# microzed_sd_v0_4.net
KiCad netlist of a schematic drawn in EAGLE
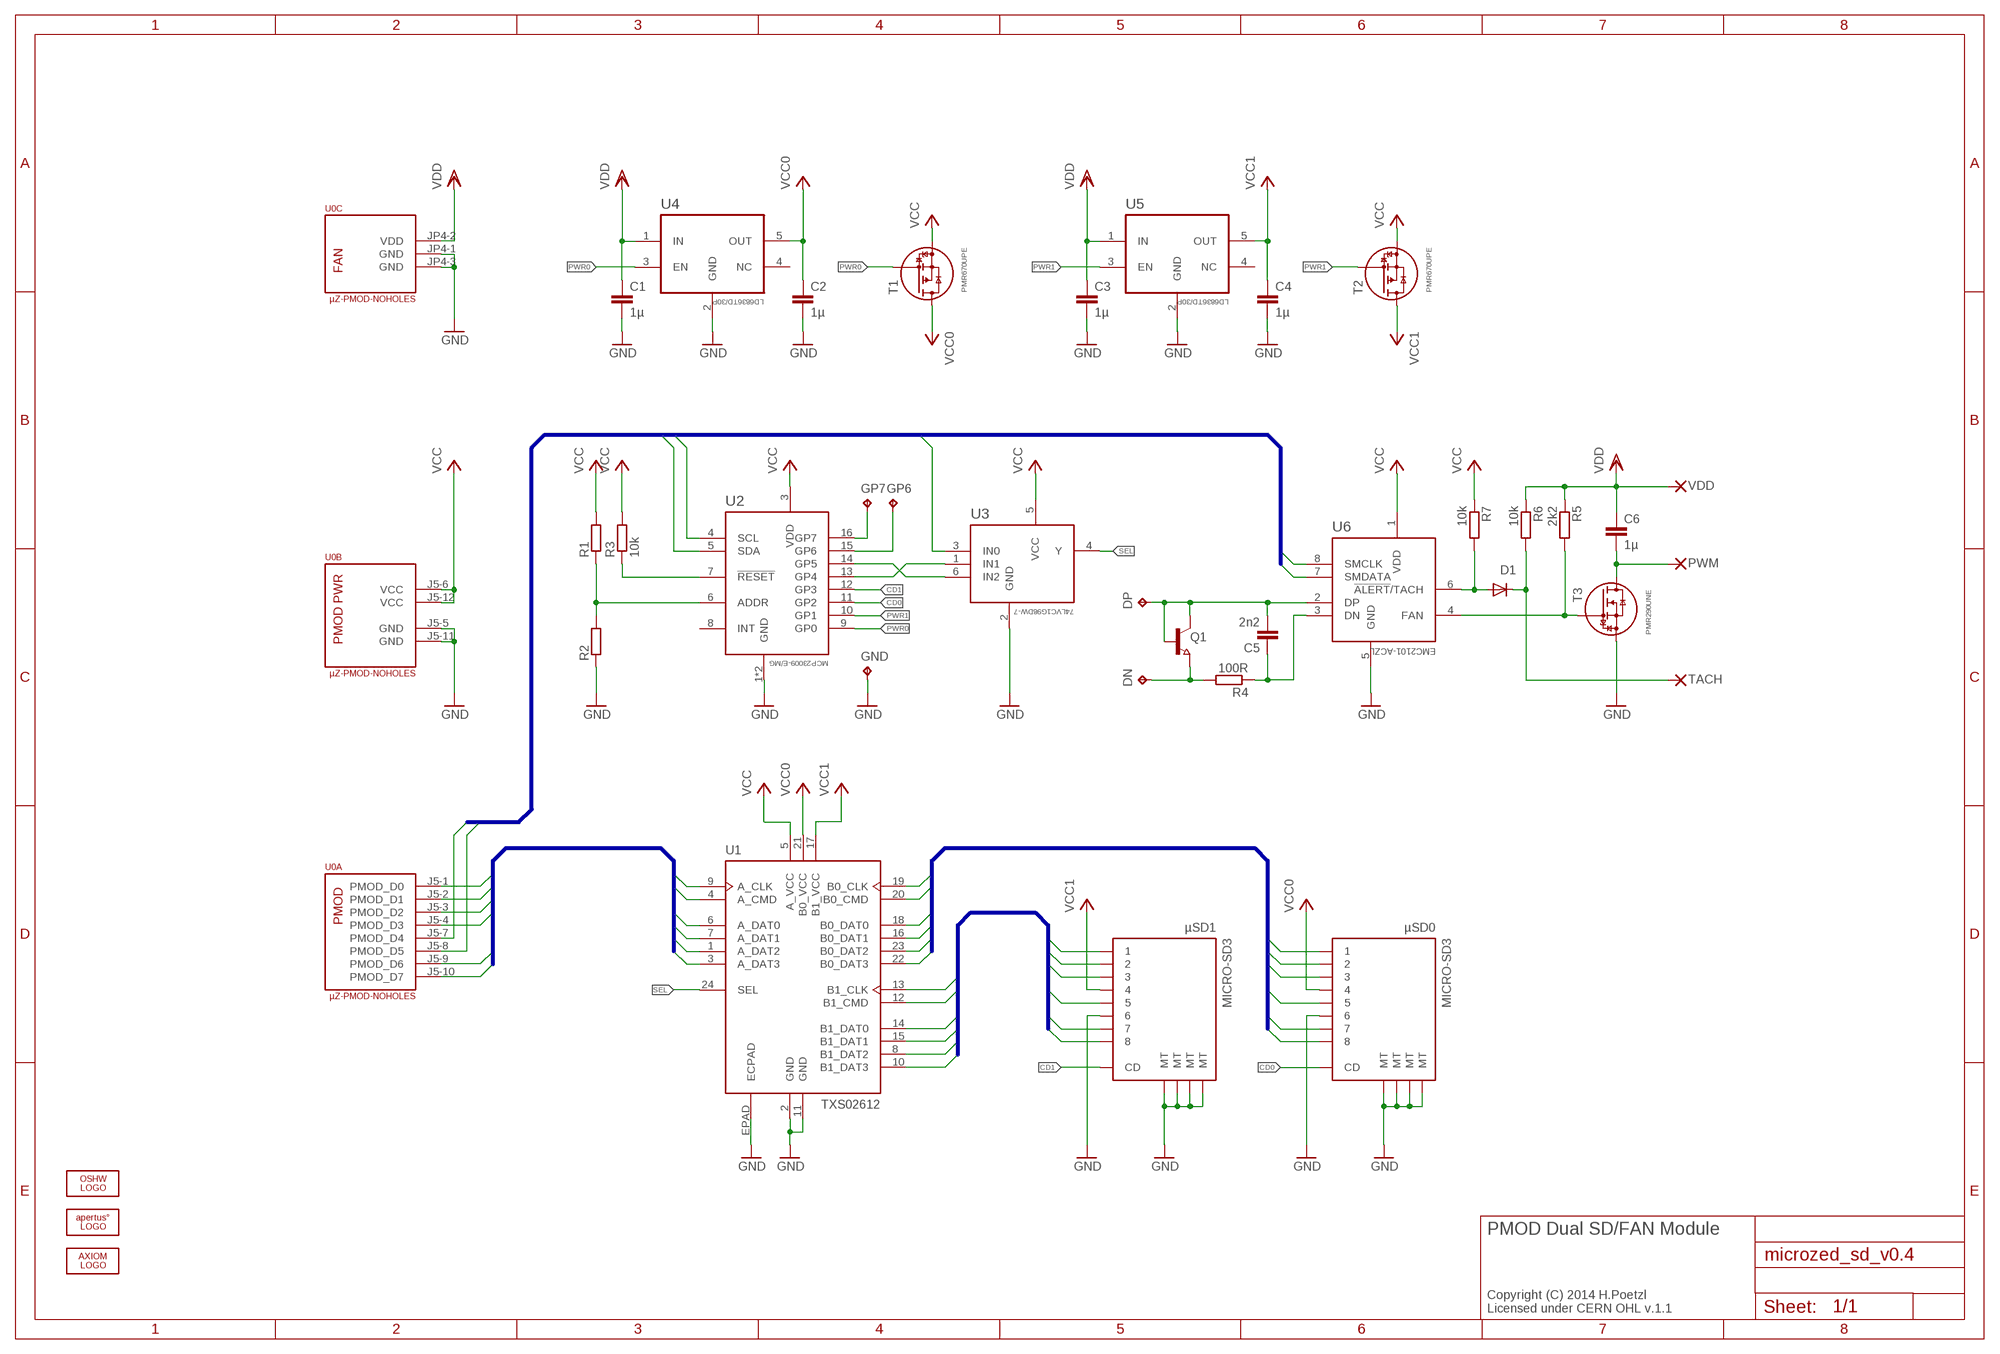
[diagram p0: schematic, sheet 1]

(export (version "E")
  (design (tool "Eeschema 10.0.6"))
  (components
    (comp (ref "C1")
      (value "1µ")
      (footprint "eagle-import:C0402K")
      (libsource (lib "eagle-import") (part "C-EUC0402K"))
    )
    (comp (ref "C2")
      (value "1µ")
      (footprint "eagle-import:C0402K")
      (libsource (lib "eagle-import") (part "C-EUC0402K"))
    )
    (comp (ref "C3")
      (value "1µ")
      (footprint "eagle-import:C0402K")
      (libsource (lib "eagle-import") (part "C-EUC0402K"))
    )
    (comp (ref "C4")
      (value "1µ")
      (footprint "eagle-import:C0402K")
      (libsource (lib "eagle-import") (part "C-EUC0402K"))
    )
    (comp (ref "C5")
      (value "2n2")
      (footprint "eagle-import:C0402K")
      (libsource (lib "eagle-import") (part "C-EUC0402K"))
    )
    (comp (ref "C6")
      (value "1µ")
      (footprint "eagle-import:C0402K")
      (libsource (lib "eagle-import") (part "C-EUC0402K"))
    )
    (comp (ref "D1")
      (value "DIODE-MICROMELF-W")
      (footprint "eagle-import:MICROMELF-W")
      (libsource (lib "eagle-import") (part "DIODE-MICROMELF-W"))
    )
    (comp (ref "DN")
      (value "TPTP20R")
      (footprint "eagle-import:TP20R")
      (libsource (lib "eagle-import") (part "TPTP20R"))
    )
    (comp (ref "DP")
      (value "TPTP20R")
      (footprint "eagle-import:TP20R")
      (libsource (lib "eagle-import") (part "TPTP20R"))
    )
    (comp (ref "GND")
      (value "TPTP20R")
      (footprint "eagle-import:TP20R")
      (libsource (lib "eagle-import") (part "TPTP20R"))
    )
    (comp (ref "GP6")
      (value "TPTP20R")
      (footprint "eagle-import:TP20R")
      (libsource (lib "eagle-import") (part "TPTP20R"))
    )
    (comp (ref "GP7")
      (value "TPTP20R")
      (footprint "eagle-import:TP20R")
      (libsource (lib "eagle-import") (part "TPTP20R"))
    )
    (comp (ref "LOGO1")
      (value "OSHW_LOGO_FILLX0100-NT")
      (footprint "eagle-import:OSHW_FILLX100_NOTEXT")
      (libsource (lib "eagle-import") (part "OSHW_LOGO_FILLX0100-NT"))
    )
    (comp (ref "PWM")
      (value "WIREPAD2,15/1,0")
      (footprint "eagle-import:2,15_1,0")
      (libsource (lib "eagle-import") (part "WIREPAD2,15/1,0"))
    )
    (comp (ref "Q1")
      (value "NPN-TRANSISTOR_SOT23")
      (footprint "eagle-import:SOT23")
      (libsource (lib "eagle-import") (part "NPN-TRANSISTOR_SOT23"))
    )
    (comp (ref "R1")
      (value "R-EU_R0603")
      (footprint "eagle-import:R0603")
      (libsource (lib "eagle-import") (part "R-EU_R0603"))
    )
    (comp (ref "R2")
      (value "R-EU_R0603")
      (footprint "eagle-import:R0603")
      (libsource (lib "eagle-import") (part "R-EU_R0603"))
    )
    (comp (ref "R3")
      (value "10k")
      (footprint "eagle-import:R0603")
      (libsource (lib "eagle-import") (part "R-EU_R0603"))
    )
    (comp (ref "R4")
      (value "100R")
      (footprint "eagle-import:R0402")
      (libsource (lib "eagle-import") (part "R-EU_R0402"))
    )
    (comp (ref "R5")
      (value "2k2")
      (footprint "eagle-import:R0402")
      (libsource (lib "eagle-import") (part "R-EU_R0402"))
    )
    (comp (ref "R6")
      (value "10k")
      (footprint "eagle-import:R0402")
      (libsource (lib "eagle-import") (part "R-EU_R0402"))
    )
    (comp (ref "R7")
      (value "10k")
      (footprint "eagle-import:R0402")
      (libsource (lib "eagle-import") (part "R-EU_R0402"))
    )
    (comp (ref "T1")
      (value "PMR670UPE")
      (footprint "eagle-import:SOT416")
      (libsource (lib "eagle-import") (part "PMR670UPE"))
    )
    (comp (ref "T2")
      (value "PMR670UPE")
      (footprint "eagle-import:SOT416")
      (libsource (lib "eagle-import") (part "PMR670UPE"))
    )
    (comp (ref "T3")
      (value "PMR290UNE")
      (footprint "eagle-import:SOT416")
      (libsource (lib "eagle-import") (part "PMR290UNE"))
    )
    (comp (ref "TACH")
      (value "WIREPAD2,15/1,0")
      (footprint "eagle-import:2,15_1,0")
      (libsource (lib "eagle-import") (part "WIREPAD2,15/1,0"))
    )
    (comp (ref "U$1")
      (value "APERTUS_LOGO334X100")
      (footprint "eagle-import:APERTUS_LOGO_334X100")
      (libsource (lib "eagle-import") (part "APERTUS_LOGO334X100"))
    )
    (comp (ref "U$13")
      (value "AXIOM_LOGO525X80")
      (footprint "eagle-import:AXIOM_LOGO_525X80")
      (libsource (lib "eagle-import") (part "AXIOM_LOGO525X80"))
    )
    (comp (ref "U0")
      (value "µZ-PMOD-NOHOLES")
      (footprint "eagle-import:µZ-TOP-NOHOLES")
      (libsource (lib "eagle-import") (part "µZ-PMOD-NOHOLES"))
    )
    (comp (ref "U1")
      (value "TXS02612")
      (footprint "eagle-import:S-PWQFN-N24")
      (libsource (lib "eagle-import") (part "TXS02612"))
    )
    (comp (ref "U2")
      (value "MCP23009-E/MG")
      (footprint "eagle-import:QFN50P300X300X80-17N")
      (libsource (lib "eagle-import") (part "MCP23009-E/MG"))
    )
    (comp (ref "U3")
      (value "74LVC1G98DW-7")
      (footprint "eagle-import:SOT65P210X110-6N")
      (libsource (lib "eagle-import") (part "74LVC1G98DW-7"))
    )
    (comp (ref "U4")
      (value "LD6836TD/30P")
      (footprint "eagle-import:SOT95P275X110-5N")
      (libsource (lib "eagle-import") (part "LD6836TD/30P"))
    )
    (comp (ref "U5")
      (value "LD6836TD/30P")
      (footprint "eagle-import:SOT95P275X110-5N")
      (libsource (lib "eagle-import") (part "LD6836TD/30P"))
    )
    (comp (ref "U6")
      (value "EMC2101-ACZL")
      (footprint "eagle-import:SOP65P490X110-8N")
      (fields (field (name "MPN") "EMC2101-ACZL-TR "))
      (libsource (lib "eagle-import") (part "EMC2101-ACZL"))
    )
    (comp (ref "VDD")
      (value "WIREPAD2,15/1,0")
      (footprint "eagle-import:2,15_1,0")
      (libsource (lib "eagle-import") (part "WIREPAD2,15/1,0"))
    )
    (comp (ref "µSD0")
      (value "MICRO-SD3")
      (footprint "eagle-import:TF-MICRO-SD_PP3")
      (libsource (lib "eagle-import") (part "MICRO-SD3"))
    )
    (comp (ref "µSD1")
      (value "MICRO-SD3")
      (footprint "eagle-import:TF-MICRO-SD_PP3")
      (libsource (lib "eagle-import") (part "MICRO-SD3"))
    )
  )
  (nets
    (net (code "1") (name "/A_CLK") (class "Default")
      (node (ref "U0") (pin "J5-4") (pinfunction "PMOD_D3_J5-4") (pintype "bidirectional"))
      (node (ref "U1") (pin "9") (pinfunction "A_CLK_9") (pintype "input"))
    )
    (net (code "2") (name "/A_CMD") (class "Default")
      (node (ref "U0") (pin "J5-3") (pinfunction "PMOD_D2_J5-3") (pintype "bidirectional"))
      (node (ref "U1") (pin "4") (pinfunction "A_CMD_4") (pintype "bidirectional"))
    )
    (net (code "3") (name "/A_DAT0") (class "Default")
      (node (ref "U0") (pin "J5-2") (pinfunction "PMOD_D1_J5-2") (pintype "bidirectional"))
      (node (ref "U1") (pin "6") (pinfunction "A_DAT0_6") (pintype "bidirectional"))
    )
    (net (code "4") (name "/A_DAT1") (class "Default")
      (node (ref "U0") (pin "J5-1") (pinfunction "PMOD_D0_J5-1") (pintype "bidirectional"))
      (node (ref "U1") (pin "7") (pinfunction "A_DAT1_7") (pintype "bidirectional"))
    )
    (net (code "5") (name "/A_DAT2") (class "Default")
      (node (ref "U0") (pin "J5-9") (pinfunction "PMOD_D6_J5-9") (pintype "bidirectional"))
      (node (ref "U1") (pin "1") (pinfunction "A_DAT2_1") (pintype "bidirectional"))
    )
    (net (code "6") (name "/A_DAT3") (class "Default")
      (node (ref "U0") (pin "J5-10") (pinfunction "PMOD_D7_J5-10") (pintype "bidirectional"))
      (node (ref "U1") (pin "3") (pinfunction "A_DAT3_3") (pintype "bidirectional"))
    )
    (net (code "7") (name "/B0_CLK") (class "Default")
      (node (ref "U1") (pin "19") (pinfunction "B0_CLK_19") (pintype "output"))
      (node (ref "µSD0") (pin "5") (pinfunction "5_5") (pintype "bidirectional"))
    )
    (net (code "8") (name "/B0_CMD") (class "Default")
      (node (ref "U1") (pin "20") (pinfunction "B0_CMD_20") (pintype "bidirectional"))
      (node (ref "µSD0") (pin "3") (pinfunction "3_3") (pintype "bidirectional"))
    )
    (net (code "9") (name "/B0_DAT0") (class "Default")
      (node (ref "U1") (pin "18") (pinfunction "B0_DAT0_18") (pintype "bidirectional"))
      (node (ref "µSD0") (pin "7") (pinfunction "7_7") (pintype "bidirectional"))
    )
    (net (code "10") (name "/B0_DAT1") (class "Default")
      (node (ref "U1") (pin "16") (pinfunction "B0_DAT1_16") (pintype "bidirectional"))
      (node (ref "µSD0") (pin "8") (pinfunction "8_8") (pintype "bidirectional"))
    )
    (net (code "11") (name "/B0_DAT2") (class "Default")
      (node (ref "U1") (pin "23") (pinfunction "B0_DAT2_23") (pintype "bidirectional"))
      (node (ref "µSD0") (pin "1") (pinfunction "1_1") (pintype "bidirectional"))
    )
    (net (code "12") (name "/B0_DAT3") (class "Default")
      (node (ref "U1") (pin "22") (pinfunction "B0_DAT3_22") (pintype "bidirectional"))
      (node (ref "µSD0") (pin "2") (pinfunction "2_2") (pintype "bidirectional"))
    )
    (net (code "13") (name "/B1_CLK") (class "Default")
      (node (ref "U1") (pin "13") (pinfunction "B1_CLK_13") (pintype "output"))
      (node (ref "µSD1") (pin "5") (pinfunction "5_5") (pintype "bidirectional"))
    )
    (net (code "14") (name "/B1_CMD") (class "Default")
      (node (ref "U1") (pin "12") (pinfunction "B1_CMD_12") (pintype "bidirectional"))
      (node (ref "µSD1") (pin "3") (pinfunction "3_3") (pintype "bidirectional"))
    )
    (net (code "15") (name "/B1_DAT0") (class "Default")
      (node (ref "U1") (pin "14") (pinfunction "B1_DAT0_14") (pintype "bidirectional"))
      (node (ref "µSD1") (pin "7") (pinfunction "7_7") (pintype "bidirectional"))
    )
    (net (code "16") (name "/B1_DAT1") (class "Default")
      (node (ref "U1") (pin "15") (pinfunction "B1_DAT1_15") (pintype "bidirectional"))
      (node (ref "µSD1") (pin "8") (pinfunction "8_8") (pintype "bidirectional"))
    )
    (net (code "17") (name "/B1_DAT2") (class "Default")
      (node (ref "U1") (pin "8") (pinfunction "B1_DAT2_8") (pintype "bidirectional"))
      (node (ref "µSD1") (pin "1") (pinfunction "1_1") (pintype "bidirectional"))
    )
    (net (code "18") (name "/B1_DAT3") (class "Default")
      (node (ref "U1") (pin "10") (pinfunction "B1_DAT3_10") (pintype "bidirectional"))
      (node (ref "µSD1") (pin "2") (pinfunction "2_2") (pintype "bidirectional"))
    )
    (net (code "19") (name "/SCL") (class "Default")
      (node (ref "U0") (pin "J5-7") (pinfunction "PMOD_D4_J5-7") (pintype "bidirectional"))
      (node (ref "U2") (pin "4") (pinfunction "SCL_4") (pintype "input"))
      (node (ref "U6") (pin "8") (pinfunction "SMCLK_8") (pintype "input"))
    )
    (net (code "20") (name "/SDA") (class "Default")
      (node (ref "U0") (pin "J5-8") (pinfunction "PMOD_D5_J5-8") (pintype "bidirectional"))
      (node (ref "U2") (pin "5") (pinfunction "SDA_5") (pintype "bidirectional"))
      (node (ref "U3") (pin "3") (pinfunction "IN0_3") (pintype "input"))
      (node (ref "U6") (pin "7") (pinfunction "SMDATA_7") (pintype "bidirectional"))
    )
    (net (code "21") (name "CD0") (class "Default")
      (node (ref "U2") (pin "11") (pinfunction "GP2_11") (pintype "bidirectional"))
      (node (ref "µSD0") (pin "CD") (pinfunction "CD_CD") (pintype "bidirectional"))
    )
    (net (code "22") (name "CD1") (class "Default")
      (node (ref "U2") (pin "12") (pinfunction "GP3_12") (pintype "bidirectional"))
      (node (ref "µSD1") (pin "CD") (pinfunction "CD_CD") (pintype "bidirectional"))
    )
    (net (code "23") (name "GND") (class "Default")
      (node (ref "C1") (pin "2") (pinfunction "2_2") (pintype "passive"))
      (node (ref "C2") (pin "2") (pinfunction "2_2") (pintype "passive"))
      (node (ref "C3") (pin "2") (pinfunction "2_2") (pintype "passive"))
      (node (ref "C4") (pin "2") (pinfunction "2_2") (pintype "passive"))
      (node (ref "GND") (pin "TP") (pinfunction "TP_TP") (pintype "input"))
      (node (ref "R2") (pin "1") (pinfunction "1_1") (pintype "passive"))
      (node (ref "T3") (pin "2") (pinfunction "S_2") (pintype "passive"))
      (node (ref "U0") (pin "J5-11") (pinfunction "GND_J5-11") (pintype "power_in"))
      (node (ref "U0") (pin "J5-5") (pinfunction "GND_J5-5") (pintype "power_in"))
      (node (ref "U0") (pin "JP4-1") (pinfunction "GND_JP4-1") (pintype "power_in"))
      (node (ref "U0") (pin "JP4-3") (pinfunction "GND_JP4-3") (pintype "power_in"))
      (node (ref "U1") (pin "11") (pinfunction "GND_11") (pintype "power_in"))
      (node (ref "U1") (pin "2") (pinfunction "GND_2") (pintype "power_in"))
      (node (ref "U1") (pin "EPAD") (pinfunction "ECPAD_EPAD") (pintype "power_in"))
      (node (ref "U2") (pin "1") (pinfunction "GND_1") (pintype "power_in"))
      (node (ref "U2") (pin "17") (pinfunction "GND_17") (pintype "power_in"))
      (node (ref "U3") (pin "2") (pinfunction "GND_2") (pintype "passive"))
      (node (ref "U4") (pin "2") (pinfunction "GND_2") (pintype "passive"))
      (node (ref "U5") (pin "2") (pinfunction "GND_2") (pintype "passive"))
      (node (ref "U6") (pin "5") (pinfunction "GND_5") (pintype "power_in"))
      (node (ref "µSD0") (pin "6") (pinfunction "6_6") (pintype "bidirectional"))
      (node (ref "µSD0") (pin "MT1") (pinfunction "MT_MT1") (pintype "power_in"))
      (node (ref "µSD0") (pin "MT2") (pinfunction "MT_MT2") (pintype "power_in"))
      (node (ref "µSD0") (pin "MT3") (pinfunction "MT_MT3") (pintype "power_in"))
      (node (ref "µSD0") (pin "MT4") (pinfunction "MT_MT4") (pintype "power_in"))
      (node (ref "µSD1") (pin "6") (pinfunction "6_6") (pintype "bidirectional"))
      (node (ref "µSD1") (pin "MT1") (pinfunction "MT_MT1") (pintype "power_in"))
      (node (ref "µSD1") (pin "MT2") (pinfunction "MT_MT2") (pintype "power_in"))
      (node (ref "µSD1") (pin "MT3") (pinfunction "MT_MT3") (pintype "power_in"))
      (node (ref "µSD1") (pin "MT4") (pinfunction "MT_MT4") (pintype "power_in"))
    )
    (net (code "24") (name "Net-(PWM-P)") (class "Default")
      (node (ref "C6") (pin "2") (pinfunction "2_2") (pintype "passive"))
      (node (ref "PWM") (pin "1") (pinfunction "P_1") (pintype "passive"))
      (node (ref "T3") (pin "3") (pinfunction "D_3") (pintype "passive"))
    )
    (net (code "25") (name "Net-(Q1-B)") (class "Default")
      (node (ref "C5") (pin "2") (pinfunction "2_2") (pintype "passive"))
      (node (ref "DP") (pin "TP") (pinfunction "TP_TP") (pintype "input"))
      (node (ref "Q1") (pin "1") (pinfunction "B_1") (pintype "passive"))
      (node (ref "Q1") (pin "3") (pinfunction "C_3") (pintype "passive"))
      (node (ref "U6") (pin "2") (pinfunction "DP_2") (pintype "passive"))
    )
    (net (code "26") (name "Net-(Q1-E)") (class "Default")
      (node (ref "DN") (pin "TP") (pinfunction "TP_TP") (pintype "input"))
      (node (ref "Q1") (pin "2") (pinfunction "E_2") (pintype "passive"))
      (node (ref "R4") (pin "2") (pinfunction "2_2") (pintype "passive"))
    )
    (net (code "27") (name "Net-(T3-G)") (class "Default")
      (node (ref "R5") (pin "2") (pinfunction "2_2") (pintype "passive"))
      (node (ref "T3") (pin "1") (pinfunction "G_1") (pintype "passive"))
      (node (ref "U6") (pin "4") (pinfunction "FAN_4") (pintype "output"))
    )
    (net (code "28") (name "Net-(TACH-P)") (class "Default")
      (node (ref "D1") (pin "C") (pinfunction "C_C") (pintype "passive"))
      (node (ref "R6") (pin "2") (pinfunction "2_2") (pintype "passive"))
      (node (ref "TACH") (pin "1") (pinfunction "P_1") (pintype "passive"))
    )
    (net (code "29") (name "Net-(U2-ADDR)") (class "Default")
      (node (ref "R1") (pin "1") (pinfunction "1_1") (pintype "passive"))
      (node (ref "R2") (pin "2") (pinfunction "2_2") (pintype "passive"))
      (node (ref "U2") (pin "6") (pinfunction "ADDR_6") (pintype "input"))
    )
    (net (code "30") (name "Net-(U2-GP4)") (class "Default")
      (node (ref "U2") (pin "13") (pinfunction "GP4_13") (pintype "bidirectional"))
      (node (ref "U3") (pin "1") (pinfunction "IN1_1") (pintype "input"))
    )
    (net (code "31") (name "Net-(U2-GP5)") (class "Default")
      (node (ref "U2") (pin "14") (pinfunction "GP5_14") (pintype "bidirectional"))
      (node (ref "U3") (pin "6") (pinfunction "IN2_6") (pintype "input"))
    )
    (net (code "32") (name "Net-(U2-GP6)") (class "Default")
      (node (ref "GP6") (pin "TP") (pinfunction "TP_TP") (pintype "input"))
      (node (ref "U2") (pin "15") (pinfunction "GP6_15") (pintype "bidirectional"))
    )
    (net (code "33") (name "Net-(U2-GP7)") (class "Default")
      (node (ref "GP7") (pin "TP") (pinfunction "TP_TP") (pintype "input"))
      (node (ref "U2") (pin "16") (pinfunction "GP7_16") (pintype "bidirectional"))
    )
    (net (code "34") (name "Net-(U2-~{RESET})") (class "Default")
      (node (ref "R3") (pin "1") (pinfunction "1_1") (pintype "passive"))
      (node (ref "U2") (pin "7") (pinfunction "~{RESET}_7") (pintype "input"))
    )
    (net (code "35") (name "Net-(U6-DN)") (class "Default")
      (node (ref "C5") (pin "1") (pinfunction "1_1") (pintype "passive"))
      (node (ref "R4") (pin "1") (pinfunction "1_1") (pintype "passive"))
      (node (ref "U6") (pin "3") (pinfunction "DN_3") (pintype "passive"))
    )
    (net (code "36") (name "Net-(U6-~{ALERT}{slash}TACH)") (class "Default")
      (node (ref "D1") (pin "A") (pinfunction "A_A") (pintype "passive"))
      (node (ref "R7") (pin "2") (pinfunction "2_2") (pintype "passive"))
      (node (ref "U6") (pin "6") (pinfunction "~{ALERT}/TACH_6") (pintype "bidirectional"))
    )
    (net (code "37") (name "PWR0") (class "Default")
      (node (ref "T1") (pin "1") (pinfunction "G_1") (pintype "passive"))
      (node (ref "U2") (pin "9") (pinfunction "GP0_9") (pintype "bidirectional"))
      (node (ref "U4") (pin "3") (pinfunction "EN_3") (pintype "input"))
    )
    (net (code "38") (name "PWR1") (class "Default")
      (node (ref "T2") (pin "1") (pinfunction "G_1") (pintype "passive"))
      (node (ref "U2") (pin "10") (pinfunction "GP1_10") (pintype "bidirectional"))
      (node (ref "U5") (pin "3") (pinfunction "EN_3") (pintype "input"))
    )
    (net (code "39") (name "SEL") (class "Default")
      (node (ref "U1") (pin "24") (pinfunction "SEL_24") (pintype "input"))
      (node (ref "U3") (pin "4") (pinfunction "Y_4") (pintype "output"))
    )
    (net (code "40") (name "VCC") (class "Default")
      (node (ref "R1") (pin "2") (pinfunction "2_2") (pintype "passive"))
      (node (ref "R3") (pin "2") (pinfunction "2_2") (pintype "passive"))
      (node (ref "R7") (pin "1") (pinfunction "1_1") (pintype "passive"))
      (node (ref "T1") (pin "2") (pinfunction "S_2") (pintype "passive"))
      (node (ref "T2") (pin "2") (pinfunction "S_2") (pintype "passive"))
      (node (ref "U0") (pin "J5-12") (pinfunction "VCC_J5-12") (pintype "power_in"))
      (node (ref "U0") (pin "J5-6") (pinfunction "VCC_J5-6") (pintype "power_in"))
      (node (ref "U1") (pin "5") (pinfunction "A_VCC_5") (pintype "power_in"))
      (node (ref "U2") (pin "3") (pinfunction "VDD_3") (pintype "power_in"))
      (node (ref "U3") (pin "5") (pinfunction "VCC_5") (pintype "power_in"))
      (node (ref "U6") (pin "1") (pinfunction "VDD_1") (pintype "power_in"))
    )
    (net (code "41") (name "VCC0") (class "Default")
      (node (ref "C2") (pin "1") (pinfunction "1_1") (pintype "passive"))
      (node (ref "T1") (pin "3") (pinfunction "D_3") (pintype "passive"))
      (node (ref "U1") (pin "21") (pinfunction "B0_VCC_21") (pintype "power_in"))
      (node (ref "U4") (pin "5") (pinfunction "OUT_5") (pintype "output"))
      (node (ref "µSD0") (pin "4") (pinfunction "4_4") (pintype "bidirectional"))
    )
    (net (code "42") (name "VCC1") (class "Default")
      (node (ref "C4") (pin "1") (pinfunction "1_1") (pintype "passive"))
      (node (ref "T2") (pin "3") (pinfunction "D_3") (pintype "passive"))
      (node (ref "U1") (pin "17") (pinfunction "B1_VCC_17") (pintype "power_in"))
      (node (ref "U5") (pin "5") (pinfunction "OUT_5") (pintype "output"))
      (node (ref "µSD1") (pin "4") (pinfunction "4_4") (pintype "bidirectional"))
    )
    (net (code "43") (name "VDD") (class "Default")
      (node (ref "C1") (pin "1") (pinfunction "1_1") (pintype "passive"))
      (node (ref "C3") (pin "1") (pinfunction "1_1") (pintype "passive"))
      (node (ref "C6") (pin "1") (pinfunction "1_1") (pintype "passive"))
      (node (ref "R5") (pin "1") (pinfunction "1_1") (pintype "passive"))
      (node (ref "R6") (pin "1") (pinfunction "1_1") (pintype "passive"))
      (node (ref "U0") (pin "JP4-2") (pinfunction "VDD_JP4-2") (pintype "power_in"))
      (node (ref "U4") (pin "1") (pinfunction "IN_1") (pintype "input"))
      (node (ref "U5") (pin "1") (pinfunction "IN_1") (pintype "input"))
      (node (ref "VDD") (pin "1") (pinfunction "P_1") (pintype "passive"))
    )
    (net (code "44") (name "unconnected-(U2-INT-Pad8)") (class "Default")
      (node (ref "U2") (pin "8") (pinfunction "INT_8") (pintype "output"))
    )
    (net (code "45") (name "unconnected-(U4-NC-Pad4)") (class "Default")
      (node (ref "U4") (pin "4") (pinfunction "NC_4") (pintype "no_connect"))
    )
    (net (code "46") (name "unconnected-(U5-NC-Pad4)") (class "Default")
      (node (ref "U5") (pin "4") (pinfunction "NC_4") (pintype "no_connect"))
    )
  )
)
